# Chronio_REV3.net
KiCad netlist of a schematic drawn in EAGLE
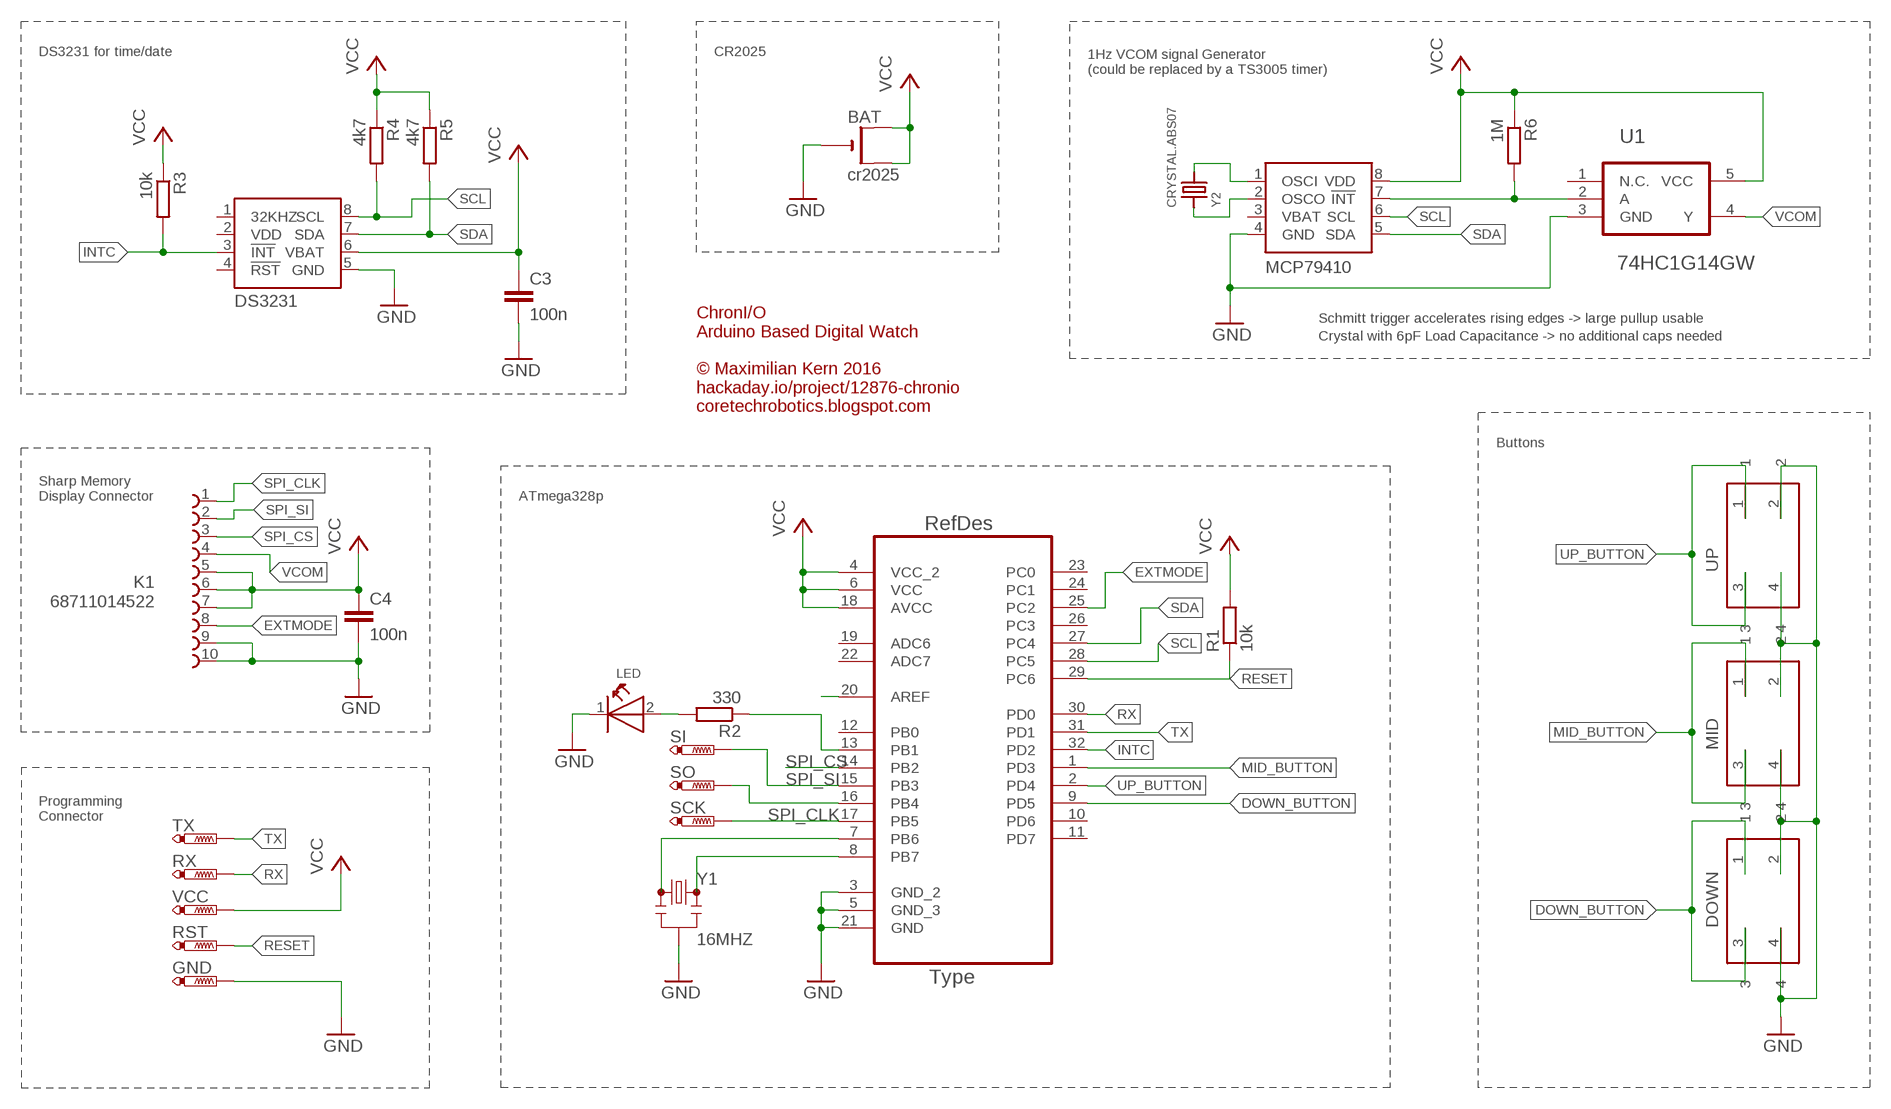
[diagram p0: schematic, sheet 1]

(export (version "E")
  (design (tool "Eeschema 10.0.6"))
  (components
    (comp (ref "ATMEGA328P")
      (value "ATMEGA328P-AU")
      (footprint "eagle-import:QFP80P900X900X120-32N")
      (libsource (lib "eagle-import") (part "ATMEGA328P-AU"))
    )
    (comp (ref "BAT")
      (value "cr2025")
      (footprint "eagle-import:CR2032-SMD")
      (libsource (lib "eagle-import") (part "CR2032SMT"))
    )
    (comp (ref "C3")
      (value "100n")
      (footprint "eagle-import:C0805")
      (libsource (lib "eagle-import") (part "C-EUC0805"))
    )
    (comp (ref "C4")
      (value "100n")
      (footprint "eagle-import:C0805")
      (libsource (lib "eagle-import") (part "C-EUC0805"))
    )
    (comp (ref "DOWN")
      (value "434331045822")
      (footprint "eagle-import:434331045822")
      (libsource (lib "eagle-import") (part "434331045822"))
    )
    (comp (ref "DS3231")
      (value "DS3231MLMD")
      (footprint "eagle-import:SO08")
      (libsource (lib "eagle-import") (part "DS3231MDLM"))
    )
    (comp (ref "GND")
      (value "PTR1TP14SQ")
      (footprint "eagle-import:TP14SQ")
      (libsource (lib "eagle-import") (part "PTR1TP14SQ"))
    )
    (comp (ref "K1")
      (value "68711014522")
      (footprint "eagle-import:68711014522")
      (libsource (lib "eagle-import") (part "68711014522"))
    )
    (comp (ref "LED")
      (value "WL-SMCW-150060GS75000-G")
      (footprint "eagle-import:0603")
      (fields
        (field (name "MANUFACTURER") "Würth Elektronik eiSos GmbH")
        (field (name "CREATED-BY") "Christin Otto")
      )
      (libsource (lib "eagle-import") (part "WL-SMCW-150060GS75000-G"))
    )
    (comp (ref "MCP79410")
      (value "PCF8523T/1LMD")
      (footprint "eagle-import:SO08")
      (libsource (lib "eagle-import") (part "PCF8523T/1DLM"))
    )
    (comp (ref "MID")
      (value "434331045822")
      (footprint "eagle-import:434331045822")
      (libsource (lib "eagle-import") (part "434331045822"))
    )
    (comp (ref "R1")
      (value "10k")
      (footprint "eagle-import:R0805")
      (libsource (lib "eagle-import") (part "R-EU_R0805"))
    )
    (comp (ref "R2")
      (value "330")
      (footprint "eagle-import:R0805")
      (libsource (lib "eagle-import") (part "R-EU_R0805"))
    )
    (comp (ref "R3")
      (value "10k")
      (footprint "eagle-import:R0805")
      (libsource (lib "eagle-import") (part "R-EU_R0805"))
    )
    (comp (ref "R4")
      (value "4k7")
      (footprint "eagle-import:R0805")
      (libsource (lib "eagle-import") (part "R-EU_R0805"))
    )
    (comp (ref "R5")
      (value "4k7")
      (footprint "eagle-import:R0805")
      (libsource (lib "eagle-import") (part "R-EU_R0805"))
    )
    (comp (ref "R6")
      (value "1M")
      (footprint "eagle-import:R0805")
      (libsource (lib "eagle-import") (part "R-EU_R0805"))
    )
    (comp (ref "RST")
      (value "PTR1TP14SQ")
      (footprint "eagle-import:TP14SQ")
      (libsource (lib "eagle-import") (part "PTR1TP14SQ"))
    )
    (comp (ref "RX")
      (value "PTR1TP14SQ")
      (footprint "eagle-import:TP14SQ")
      (libsource (lib "eagle-import") (part "PTR1TP14SQ"))
    )
    (comp (ref "SCK")
      (value "PTR1TP14SQ")
      (footprint "eagle-import:TP14SQ")
      (libsource (lib "eagle-import") (part "PTR1TP14SQ"))
    )
    (comp (ref "SI")
      (value "PTR1TP14SQ")
      (footprint "eagle-import:TP14SQ")
      (libsource (lib "eagle-import") (part "PTR1TP14SQ"))
    )
    (comp (ref "SO")
      (value "PTR1TP14SQ")
      (footprint "eagle-import:TP14SQ")
      (libsource (lib "eagle-import") (part "PTR1TP14SQ"))
    )
    (comp (ref "TX")
      (value "PTR1TP14SQ")
      (footprint "eagle-import:TP14SQ")
      (libsource (lib "eagle-import") (part "PTR1TP14SQ"))
    )
    (comp (ref "U1")
      (value "74HC1G14GW")
      (footprint "eagle-import:SOT65P210X110-5N")
      (libsource (lib "eagle-import") (part "74HC1G14GW"))
    )
    (comp (ref "UP")
      (value "434331045822")
      (footprint "eagle-import:434331045822")
      (libsource (lib "eagle-import") (part "434331045822"))
    )
    (comp (ref "VCC")
      (value "PTR1TP14SQ")
      (footprint "eagle-import:TP14SQ")
      (libsource (lib "eagle-import") (part "PTR1TP14SQ"))
    )
    (comp (ref "Y1")
      (value "16MHZ")
      (footprint "eagle-import:RESONATOR-SMD")
      (libsource (lib "eagle-import") (part "RESONATOR16MHZ"))
    )
    (comp (ref "Y2")
      (value "CRYSTAL.ABS07")
      (footprint "eagle-import:ABS07")
      (libsource (lib "eagle-import") (part "CRYSTAL.ABS07"))
    )
  )
  (nets
    (net (code "1") (name "/VBAT") (class "Default")
      (node (ref "MCP79410") (pin "3") (pinfunction "VBAT_3") (pintype "power_in"))
    )
    (net (code "2") (name "/VDD") (class "Default")
      (node (ref "DS3231") (pin "2") (pinfunction "VDD_2") (pintype "power_in"))
    )
    (net (code "3") (name "DOWN_BUTTON") (class "Default")
      (node (ref "ATMEGA328P") (pin "9") (pinfunction "PD5_9") (pintype "bidirectional"))
      (node (ref "DOWN") (pin "1") (pinfunction "1_1") (pintype "bidirectional"))
      (node (ref "DOWN") (pin "3") (pinfunction "3_3") (pintype "bidirectional"))
    )
    (net (code "4") (name "EXTMODE") (class "Default")
      (node (ref "ATMEGA328P") (pin "25") (pinfunction "PC2_25") (pintype "bidirectional"))
      (node (ref "K1") (pin "8") (pinfunction "8_8") (pintype "passive"))
    )
    (net (code "5") (name "GND") (class "Default")
      (node (ref "ATMEGA328P") (pin "21") (pinfunction "GND_21") (pintype "passive"))
      (node (ref "ATMEGA328P") (pin "3") (pinfunction "GND_2_3") (pintype "passive"))
      (node (ref "ATMEGA328P") (pin "5") (pinfunction "GND_3_5") (pintype "passive"))
      (node (ref "BAT") (pin "-") (pinfunction "-_-") (pintype "passive"))
      (node (ref "C3") (pin "2") (pinfunction "2_2") (pintype "passive"))
      (node (ref "C4") (pin "2") (pinfunction "2_2") (pintype "passive"))
      (node (ref "DOWN") (pin "2") (pinfunction "2_2") (pintype "bidirectional"))
      (node (ref "DOWN") (pin "4") (pinfunction "4_4") (pintype "bidirectional"))
      (node (ref "DS3231") (pin "5") (pinfunction "GND_5") (pintype "power_in"))
      (node (ref "GND") (pin "TP") (pinfunction "TP_TP") (pintype "input"))
      (node (ref "K1") (pin "10") (pinfunction "10_10") (pintype "passive"))
      (node (ref "K1") (pin "9") (pinfunction "9_9") (pintype "passive"))
      (node (ref "LED") (pin "1") (pinfunction "K_1") (pintype "bidirectional"))
      (node (ref "MCP79410") (pin "4") (pinfunction "GND_4") (pintype "power_in"))
      (node (ref "MID") (pin "2") (pinfunction "2_2") (pintype "bidirectional"))
      (node (ref "MID") (pin "4") (pinfunction "4_4") (pintype "bidirectional"))
      (node (ref "U1") (pin "3") (pinfunction "GND_3") (pintype "passive"))
      (node (ref "UP") (pin "2") (pinfunction "2_2") (pintype "bidirectional"))
      (node (ref "UP") (pin "4") (pinfunction "4_4") (pintype "bidirectional"))
      (node (ref "Y1") (pin "2") (pinfunction "2_2") (pintype "passive"))
    )
    (net (code "6") (name "INTC") (class "Default")
      (node (ref "ATMEGA328P") (pin "32") (pinfunction "PD2_32") (pintype "bidirectional"))
      (node (ref "DS3231") (pin "3") (pinfunction "~{INT}_3") (pintype "output"))
      (node (ref "R3") (pin "2") (pinfunction "2_2") (pintype "passive"))
    )
    (net (code "7") (name "MID_BUTTON") (class "Default")
      (node (ref "ATMEGA328P") (pin "1") (pinfunction "PD3_1") (pintype "bidirectional"))
      (node (ref "MID") (pin "1") (pinfunction "1_1") (pintype "bidirectional"))
      (node (ref "MID") (pin "3") (pinfunction "3_3") (pintype "bidirectional"))
    )
    (net (code "8") (name "Net-(ATMEGA328P-PB1)") (class "Default")
      (node (ref "ATMEGA328P") (pin "13") (pinfunction "PB1_13") (pintype "bidirectional"))
      (node (ref "R2") (pin "1") (pinfunction "1_1") (pintype "passive"))
    )
    (net (code "9") (name "Net-(ATMEGA328P-PB4)") (class "Default")
      (node (ref "ATMEGA328P") (pin "16") (pinfunction "PB4_16") (pintype "bidirectional"))
      (node (ref "SO") (pin "TP") (pinfunction "TP_TP") (pintype "input"))
    )
    (net (code "10") (name "Net-(ATMEGA328P-PB6)") (class "Default")
      (node (ref "ATMEGA328P") (pin "7") (pinfunction "PB6_7") (pintype "bidirectional"))
      (node (ref "Y1") (pin "1") (pinfunction "1_1") (pintype "passive"))
    )
    (net (code "11") (name "Net-(ATMEGA328P-PB7)") (class "Default")
      (node (ref "ATMEGA328P") (pin "8") (pinfunction "PB7_8") (pintype "bidirectional"))
      (node (ref "Y1") (pin "3") (pinfunction "3_3") (pintype "passive"))
    )
    (net (code "12") (name "Net-(LED-A)") (class "Default")
      (node (ref "LED") (pin "2") (pinfunction "A_2") (pintype "bidirectional"))
      (node (ref "R2") (pin "2") (pinfunction "2_2") (pintype "passive"))
    )
    (net (code "13") (name "Net-(MCP79410-OSCI)") (class "Default")
      (node (ref "MCP79410") (pin "1") (pinfunction "OSCI_1") (pintype "input"))
      (node (ref "Y2") (pin "2") (pinfunction "2_2") (pintype "passive"))
    )
    (net (code "14") (name "Net-(MCP79410-OSCO)") (class "Default")
      (node (ref "MCP79410") (pin "2") (pinfunction "OSCO_2") (pintype "output"))
      (node (ref "Y2") (pin "1") (pinfunction "1_1") (pintype "passive"))
    )
    (net (code "15") (name "Net-(MCP79410-~{INT})") (class "Default")
      (node (ref "MCP79410") (pin "7") (pinfunction "~{INT}_7") (pintype "output"))
      (node (ref "R6") (pin "2") (pinfunction "2_2") (pintype "passive"))
      (node (ref "U1") (pin "2") (pinfunction "A_2") (pintype "input"))
    )
    (net (code "16") (name "RESET") (class "Default")
      (node (ref "ATMEGA328P") (pin "29") (pinfunction "PC6_29") (pintype "bidirectional"))
      (node (ref "R1") (pin "1") (pinfunction "1_1") (pintype "passive"))
      (node (ref "RST") (pin "TP") (pinfunction "TP_TP") (pintype "input"))
    )
    (net (code "17") (name "RX") (class "Default")
      (node (ref "ATMEGA328P") (pin "30") (pinfunction "PD0_30") (pintype "bidirectional"))
      (node (ref "RX") (pin "TP") (pinfunction "TP_TP") (pintype "input"))
    )
    (net (code "18") (name "SCL") (class "Default")
      (node (ref "ATMEGA328P") (pin "28") (pinfunction "PC5_28") (pintype "bidirectional"))
      (node (ref "DS3231") (pin "8") (pinfunction "SCL_8") (pintype "input"))
      (node (ref "MCP79410") (pin "6") (pinfunction "SCL_6") (pintype "bidirectional"))
      (node (ref "R4") (pin "2") (pinfunction "2_2") (pintype "passive"))
    )
    (net (code "19") (name "SDA") (class "Default")
      (node (ref "ATMEGA328P") (pin "27") (pinfunction "PC4_27") (pintype "bidirectional"))
      (node (ref "DS3231") (pin "7") (pinfunction "SDA_7") (pintype "input"))
      (node (ref "MCP79410") (pin "5") (pinfunction "SDA_5") (pintype "bidirectional"))
      (node (ref "R5") (pin "2") (pinfunction "2_2") (pintype "passive"))
    )
    (net (code "20") (name "SPI_CLK") (class "Default")
      (node (ref "ATMEGA328P") (pin "17") (pinfunction "PB5_17") (pintype "bidirectional"))
      (node (ref "K1") (pin "1") (pinfunction "1_1") (pintype "passive"))
      (node (ref "SCK") (pin "TP") (pinfunction "TP_TP") (pintype "input"))
    )
    (net (code "21") (name "SPI_CS") (class "Default")
      (node (ref "ATMEGA328P") (pin "14") (pinfunction "PB2_14") (pintype "bidirectional"))
      (node (ref "K1") (pin "3") (pinfunction "3_3") (pintype "passive"))
    )
    (net (code "22") (name "SPI_SI") (class "Default")
      (node (ref "ATMEGA328P") (pin "15") (pinfunction "PB3_15") (pintype "bidirectional"))
      (node (ref "K1") (pin "2") (pinfunction "2_2") (pintype "passive"))
      (node (ref "SI") (pin "TP") (pinfunction "TP_TP") (pintype "input"))
    )
    (net (code "23") (name "TX") (class "Default")
      (node (ref "ATMEGA328P") (pin "31") (pinfunction "PD1_31") (pintype "bidirectional"))
      (node (ref "TX") (pin "TP") (pinfunction "TP_TP") (pintype "input"))
    )
    (net (code "24") (name "UP_BUTTON") (class "Default")
      (node (ref "ATMEGA328P") (pin "2") (pinfunction "PD4_2") (pintype "bidirectional"))
      (node (ref "UP") (pin "1") (pinfunction "1_1") (pintype "bidirectional"))
      (node (ref "UP") (pin "3") (pinfunction "3_3") (pintype "bidirectional"))
    )
    (net (code "25") (name "VCC") (class "Default")
      (node (ref "ATMEGA328P") (pin "18") (pinfunction "AVCC_18") (pintype "power_in"))
      (node (ref "ATMEGA328P") (pin "4") (pinfunction "VCC_2_4") (pintype "power_in"))
      (node (ref "ATMEGA328P") (pin "6") (pinfunction "VCC_6") (pintype "power_in"))
      (node (ref "BAT") (pin "+$1") (pinfunction "+_+$1") (pintype "passive"))
      (node (ref "BAT") (pin "+$2") (pinfunction "+1_+$2") (pintype "passive"))
      (node (ref "C3") (pin "1") (pinfunction "1_1") (pintype "passive"))
      (node (ref "C4") (pin "1") (pinfunction "1_1") (pintype "passive"))
      (node (ref "DS3231") (pin "6") (pinfunction "VBAT_6") (pintype "power_in"))
      (node (ref "K1") (pin "5") (pinfunction "5_5") (pintype "passive"))
      (node (ref "K1") (pin "6") (pinfunction "6_6") (pintype "passive"))
      (node (ref "K1") (pin "7") (pinfunction "7_7") (pintype "passive"))
      (node (ref "MCP79410") (pin "8") (pinfunction "VDD_8") (pintype "power_in"))
      (node (ref "R1") (pin "2") (pinfunction "2_2") (pintype "passive"))
      (node (ref "R3") (pin "1") (pinfunction "1_1") (pintype "passive"))
      (node (ref "R4") (pin "1") (pinfunction "1_1") (pintype "passive"))
      (node (ref "R5") (pin "1") (pinfunction "1_1") (pintype "passive"))
      (node (ref "R6") (pin "1") (pinfunction "1_1") (pintype "passive"))
      (node (ref "U1") (pin "5") (pinfunction "VCC_5") (pintype "power_in"))
      (node (ref "VCC") (pin "TP") (pinfunction "TP_TP") (pintype "input"))
    )
    (net (code "26") (name "VCOM") (class "Default")
      (node (ref "K1") (pin "4") (pinfunction "4_4") (pintype "passive"))
      (node (ref "U1") (pin "4") (pinfunction "Y_4") (pintype "output"))
    )
    (net (code "27") (name "unconnected-(ATMEGA328P-ADC6-Pad19)") (class "Default")
      (node (ref "ATMEGA328P") (pin "19") (pinfunction "ADC6_19") (pintype "input"))
    )
    (net (code "28") (name "unconnected-(ATMEGA328P-ADC7-Pad22)") (class "Default")
      (node (ref "ATMEGA328P") (pin "22") (pinfunction "ADC7_22") (pintype "input"))
    )
    (net (code "29") (name "unconnected-(ATMEGA328P-AREF-Pad20)") (class "Default")
      (node (ref "ATMEGA328P") (pin "20") (pinfunction "AREF_20") (pintype "input"))
    )
    (net (code "30") (name "unconnected-(ATMEGA328P-PB0-Pad12)") (class "Default")
      (node (ref "ATMEGA328P") (pin "12") (pinfunction "PB0_12") (pintype "bidirectional"))
    )
    (net (code "31") (name "unconnected-(ATMEGA328P-PC0-Pad23)") (class "Default")
      (node (ref "ATMEGA328P") (pin "23") (pinfunction "PC0_23") (pintype "bidirectional"))
    )
    (net (code "32") (name "unconnected-(ATMEGA328P-PC1-Pad24)") (class "Default")
      (node (ref "ATMEGA328P") (pin "24") (pinfunction "PC1_24") (pintype "bidirectional"))
    )
    (net (code "33") (name "unconnected-(ATMEGA328P-PC3-Pad26)") (class "Default")
      (node (ref "ATMEGA328P") (pin "26") (pinfunction "PC3_26") (pintype "bidirectional"))
    )
    (net (code "34") (name "unconnected-(ATMEGA328P-PD6-Pad10)") (class "Default")
      (node (ref "ATMEGA328P") (pin "10") (pinfunction "PD6_10") (pintype "bidirectional"))
    )
    (net (code "35") (name "unconnected-(ATMEGA328P-PD7-Pad11)") (class "Default")
      (node (ref "ATMEGA328P") (pin "11") (pinfunction "PD7_11") (pintype "bidirectional"))
    )
    (net (code "36") (name "unconnected-(DS3231-32KHZ-Pad1)") (class "Default")
      (node (ref "DS3231") (pin "1") (pinfunction "32KHZ_1") (pintype "output"))
    )
    (net (code "37") (name "unconnected-(DS3231-~{RST}-Pad4)") (class "Default")
      (node (ref "DS3231") (pin "4") (pinfunction "~{RST}_4") (pintype "input"))
    )
    (net (code "38") (name "unconnected-(U1-N.C.-Pad1)") (class "Default")
      (node (ref "U1") (pin "1") (pinfunction "N.C._1") (pintype "no_connect"))
    )
  )
)
